# SCH_myMCP23017_2023-06-13.net
KiCad netlist of a schematic drawn in EasyEDA
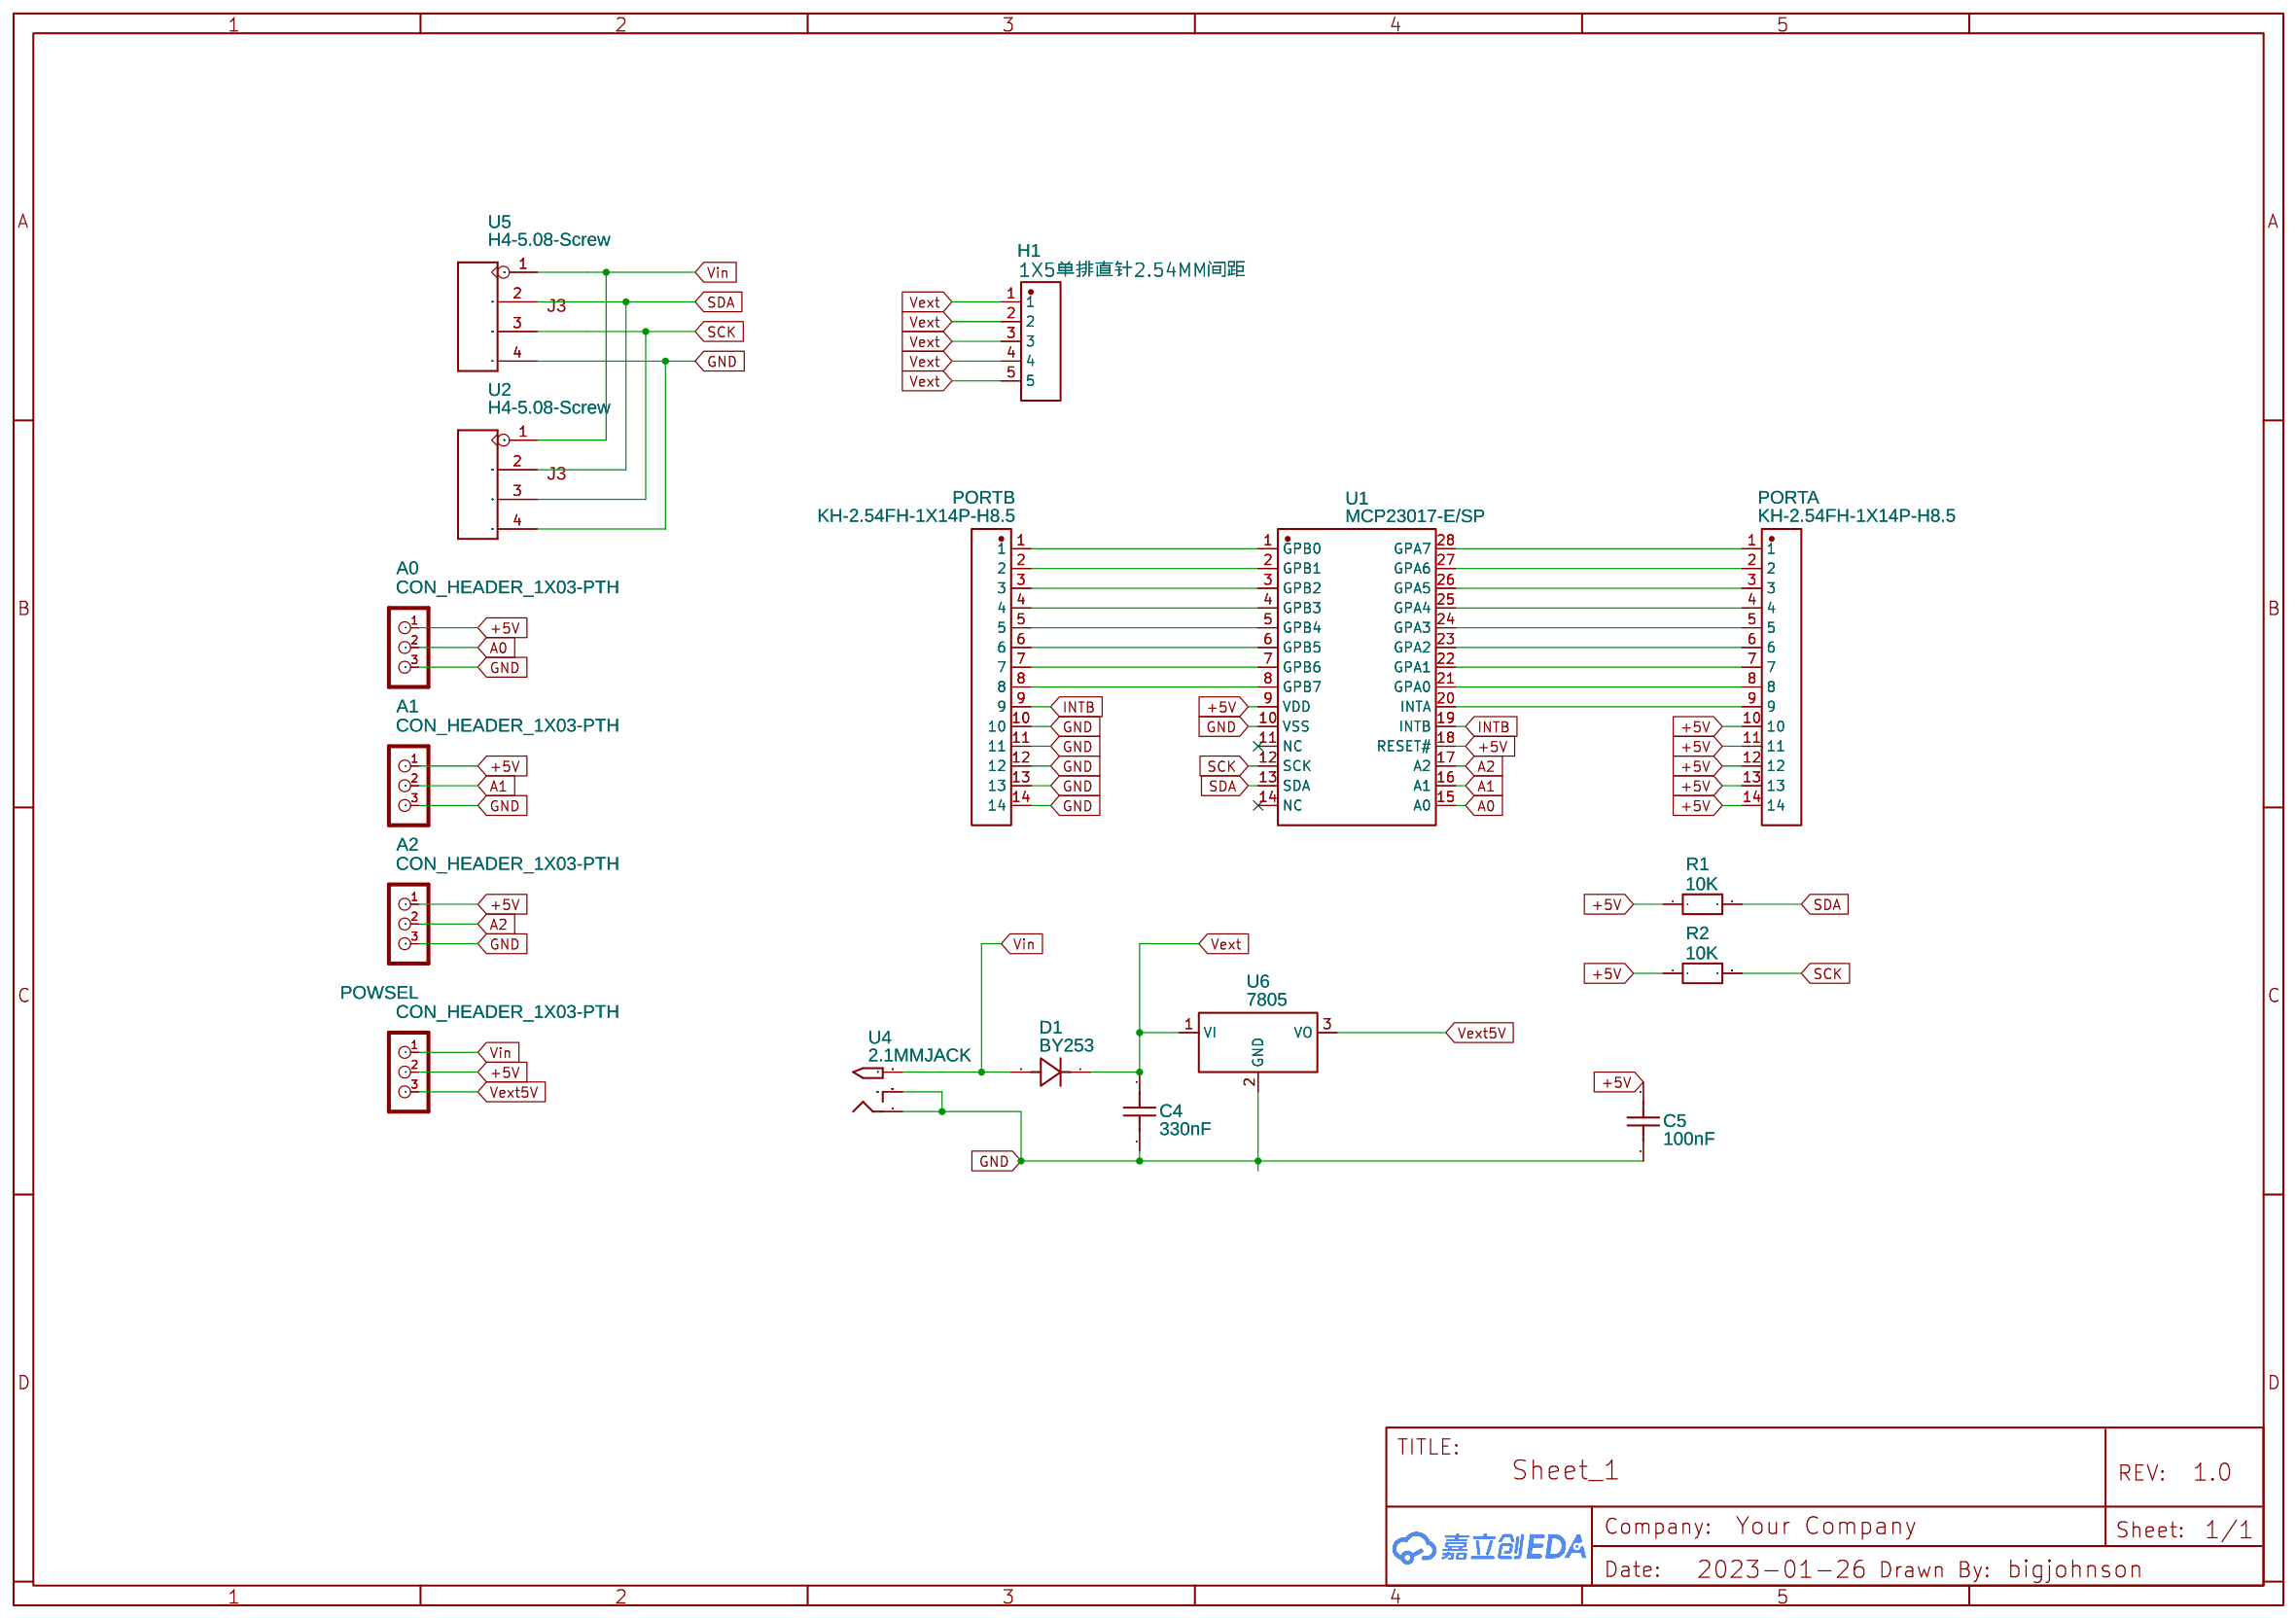
[diagram p0: schematic sheet]

(export (version "E")
  (design (tool "Eeschema 10.0.6"))
  (components
    (comp (ref "A0") (value "CON_HEADER_1X03-PTH") (libsource (lib "") (part "CON_HEADER_1X03-PTH")))
    (comp (ref "A1") (value "CON_HEADER_1X03-PTH") (libsource (lib "") (part "CON_HEADER_1X03-PTH")))
    (comp (ref "A2") (value "CON_HEADER_1X03-PTH") (libsource (lib "") (part "CON_HEADER_1X03-PTH")))
    (comp (ref "C4")
      (value "330nF")
      (fields
        (field (name "BOM_Manufacturer Part") "CT4-0805B103 K500")
        (field (name "BOM_Supplier Part") "C8033")
      )
      (libsource (lib "") (part "CT4-0805B103 K500"))
    )
    (comp (ref "C5")
      (value "100nF")
      (fields
        (field (name "BOM_Manufacturer Part") "CT4-0805B103 K500")
        (field (name "BOM_Supplier Part") "C8033")
      )
      (libsource (lib "") (part "CT4-0805B103 K500"))
    )
    (comp (ref "D1")
      (value "BY253")
      (fields (field (name "BOM_Manufacturer Part") "MUR460") (field (name "BOM_Supplier Part") "C2990844"))
      (libsource (lib "") (part "MUR460_C2990844"))
    )
    (comp (ref "H1")
      (value "1X5单排直针2.54MM间距")
      (fields
        (field (name "BOM_Manufacturer Part") "1x5单排直针2.54mm间距")
        (field (name "BOM_Supplier Part") "C9900017403")
      )
      (libsource (lib "") (part "1X5单排直针2.54MM间距"))
    )
    (comp (ref "PORTA")
      (value "KH-2.54FH-1X14P-H8.5")
      (fields (field (name "BOM_Supplier Part") "C2905420"))
      (libsource (lib "") (part "KH-2.54FH-1X14P-H8.5_1"))
    )
    (comp (ref "PORTB")
      (value "KH-2.54FH-1X14P-H8.5")
      (fields (field (name "BOM_Supplier Part") "C2905420"))
      (libsource (lib "") (part "KH-2.54FH-1X14P-H8.5"))
    )
    (comp (ref "POWSEL") (value "CON_HEADER_1X03-PTH") (libsource (lib "") (part "CON_HEADER_1X03-PTH_1")))
    (comp (ref "R1") (value "10K") (libsource (lib "") (part "Res_AXIAL-0.4(1/4W)_EU")))
    (comp (ref "R2") (value "10K") (libsource (lib "") (part "Res_AXIAL-0.4(1/4W)_EU")))
    (comp (ref "U1")
      (value "MCP23017-E/SP")
      (fields (field (name "BOM_Supplier Part") "C647352"))
      (libsource (lib "") (part "MCP23017-E/SP"))
    )
    (comp (ref "U2") (value "H4-5.08-Screw") (libsource (lib "") (part "H4-5.08-Screw")))
    (comp (ref "U4") (value "2.1MMJACK") (libsource (lib "") (part "2.1MMJACK")))
    (comp (ref "U5") (value "H4-5.08-Screw") (libsource (lib "") (part "H4-5.08-Screw")))
    (comp (ref "U6")
      (value "7805")
      (fields (field (name "BOM_Supplier Part") "C305416"))
      (libsource (lib "") (part "7805"))
    )
  )
  (nets
    (net (code "1") (name "+5V") (class "Default")
      (node (ref "A0") (pin "1") (pinfunction "1_1") (pintype "unspecified"))
      (node (ref "A1") (pin "1") (pinfunction "1_1") (pintype "unspecified"))
      (node (ref "A2") (pin "1") (pinfunction "1_1") (pintype "unspecified"))
      (node (ref "C5") (pin "1") (pinfunction "1_1") (pintype "unspecified"))
      (node (ref "PORTA") (pin "10") (pinfunction "10_10") (pintype "unspecified"))
      (node (ref "PORTA") (pin "11") (pinfunction "11_11") (pintype "unspecified"))
      (node (ref "PORTA") (pin "12") (pinfunction "12_12") (pintype "unspecified"))
      (node (ref "PORTA") (pin "13") (pinfunction "13_13") (pintype "unspecified"))
      (node (ref "PORTA") (pin "14") (pinfunction "14_14") (pintype "unspecified"))
      (node (ref "POWSEL") (pin "2") (pinfunction "2_2") (pintype "unspecified"))
      (node (ref "R1") (pin "1") (pinfunction "1_1") (pintype "unspecified"))
      (node (ref "R2") (pin "1") (pinfunction "1_1") (pintype "unspecified"))
      (node (ref "U1") (pin "18") (pinfunction "RESET#_18") (pintype "unspecified"))
      (node (ref "U1") (pin "9") (pinfunction "VDD_9") (pintype "unspecified"))
    )
    (net (code "2") (name "A0") (class "Default")
      (node (ref "A0") (pin "2") (pinfunction "2_2") (pintype "unspecified"))
      (node (ref "U1") (pin "15") (pinfunction "A0_15") (pintype "unspecified"))
    )
    (net (code "3") (name "A1") (class "Default")
      (node (ref "A1") (pin "2") (pinfunction "2_2") (pintype "unspecified"))
      (node (ref "U1") (pin "16") (pinfunction "A1_16") (pintype "unspecified"))
    )
    (net (code "4") (name "A2") (class "Default")
      (node (ref "A2") (pin "2") (pinfunction "2_2") (pintype "unspecified"))
      (node (ref "U1") (pin "17") (pinfunction "A2_17") (pintype "unspecified"))
    )
    (net (code "5") (name "GND") (class "Default")
      (node (ref "A0") (pin "3") (pinfunction "3_3") (pintype "unspecified"))
      (node (ref "A1") (pin "3") (pinfunction "3_3") (pintype "unspecified"))
      (node (ref "A2") (pin "3") (pinfunction "3_3") (pintype "unspecified"))
      (node (ref "C4") (pin "2") (pinfunction "2_2") (pintype "unspecified"))
      (node (ref "C5") (pin "2") (pinfunction "2_2") (pintype "unspecified"))
      (node (ref "PORTB") (pin "10") (pinfunction "10_10") (pintype "unspecified"))
      (node (ref "PORTB") (pin "11") (pinfunction "11_11") (pintype "unspecified"))
      (node (ref "PORTB") (pin "12") (pinfunction "12_12") (pintype "unspecified"))
      (node (ref "PORTB") (pin "13") (pinfunction "13_13") (pintype "unspecified"))
      (node (ref "PORTB") (pin "14") (pinfunction "14_14") (pintype "unspecified"))
      (node (ref "U1") (pin "10") (pinfunction "VSS_10") (pintype "unspecified"))
      (node (ref "U2") (pin "4") (pinfunction "P$4_4") (pintype "unspecified"))
      (node (ref "U4") (pin "RING") (pinfunction "RING_RING") (pintype "unspecified"))
      (node (ref "U4") (pin "RING_SW") (pinfunction "RING_SW_RING_SW") (pintype "unspecified"))
      (node (ref "U5") (pin "4") (pinfunction "P$4_4") (pintype "unspecified"))
      (node (ref "U6") (pin "2") (pinfunction "GND_2") (pintype "unspecified"))
    )
    (net (code "6") (name "INTB") (class "Default")
      (node (ref "PORTB") (pin "9") (pinfunction "9_9") (pintype "unspecified"))
      (node (ref "U1") (pin "19") (pinfunction "INTB_19") (pintype "unspecified"))
    )
    (net (code "7") (name "Net-(U1-GPA0)") (class "Default")
      (node (ref "PORTA") (pin "8") (pinfunction "8_8") (pintype "unspecified"))
      (node (ref "U1") (pin "21") (pinfunction "GPA0_21") (pintype "unspecified"))
    )
    (net (code "8") (name "Net-(U1-GPA1)") (class "Default")
      (node (ref "PORTA") (pin "7") (pinfunction "7_7") (pintype "unspecified"))
      (node (ref "U1") (pin "22") (pinfunction "GPA1_22") (pintype "unspecified"))
    )
    (net (code "9") (name "Net-(U1-GPA2)") (class "Default")
      (node (ref "PORTA") (pin "6") (pinfunction "6_6") (pintype "unspecified"))
      (node (ref "U1") (pin "23") (pinfunction "GPA2_23") (pintype "unspecified"))
    )
    (net (code "10") (name "Net-(U1-GPA3)") (class "Default")
      (node (ref "PORTA") (pin "5") (pinfunction "5_5") (pintype "unspecified"))
      (node (ref "U1") (pin "24") (pinfunction "GPA3_24") (pintype "unspecified"))
    )
    (net (code "11") (name "Net-(U1-GPA4)") (class "Default")
      (node (ref "PORTA") (pin "4") (pinfunction "4_4") (pintype "unspecified"))
      (node (ref "U1") (pin "25") (pinfunction "GPA4_25") (pintype "unspecified"))
    )
    (net (code "12") (name "Net-(U1-GPA5)") (class "Default")
      (node (ref "PORTA") (pin "3") (pinfunction "3_3") (pintype "unspecified"))
      (node (ref "U1") (pin "26") (pinfunction "GPA5_26") (pintype "unspecified"))
    )
    (net (code "13") (name "Net-(U1-GPA6)") (class "Default")
      (node (ref "PORTA") (pin "2") (pinfunction "2_2") (pintype "unspecified"))
      (node (ref "U1") (pin "27") (pinfunction "GPA6_27") (pintype "unspecified"))
    )
    (net (code "14") (name "Net-(U1-GPA7)") (class "Default")
      (node (ref "PORTA") (pin "1") (pinfunction "1_1") (pintype "unspecified"))
      (node (ref "U1") (pin "28") (pinfunction "GPA7_28") (pintype "unspecified"))
    )
    (net (code "15") (name "Net-(U1-GPB0)") (class "Default")
      (node (ref "PORTB") (pin "1") (pinfunction "1_1") (pintype "unspecified"))
      (node (ref "U1") (pin "1") (pinfunction "GPB0_1") (pintype "unspecified"))
    )
    (net (code "16") (name "Net-(U1-GPB1)") (class "Default")
      (node (ref "PORTB") (pin "2") (pinfunction "2_2") (pintype "unspecified"))
      (node (ref "U1") (pin "2") (pinfunction "GPB1_2") (pintype "unspecified"))
    )
    (net (code "17") (name "Net-(U1-GPB2)") (class "Default")
      (node (ref "PORTB") (pin "3") (pinfunction "3_3") (pintype "unspecified"))
      (node (ref "U1") (pin "3") (pinfunction "GPB2_3") (pintype "unspecified"))
    )
    (net (code "18") (name "Net-(U1-GPB3)") (class "Default")
      (node (ref "PORTB") (pin "4") (pinfunction "4_4") (pintype "unspecified"))
      (node (ref "U1") (pin "4") (pinfunction "GPB3_4") (pintype "unspecified"))
    )
    (net (code "19") (name "Net-(U1-GPB4)") (class "Default")
      (node (ref "PORTB") (pin "5") (pinfunction "5_5") (pintype "unspecified"))
      (node (ref "U1") (pin "5") (pinfunction "GPB4_5") (pintype "unspecified"))
    )
    (net (code "20") (name "Net-(U1-GPB5)") (class "Default")
      (node (ref "PORTB") (pin "6") (pinfunction "6_6") (pintype "unspecified"))
      (node (ref "U1") (pin "6") (pinfunction "GPB5_6") (pintype "unspecified"))
    )
    (net (code "21") (name "Net-(U1-GPB6)") (class "Default")
      (node (ref "PORTB") (pin "7") (pinfunction "7_7") (pintype "unspecified"))
      (node (ref "U1") (pin "7") (pinfunction "GPB6_7") (pintype "unspecified"))
    )
    (net (code "22") (name "Net-(U1-GPB7)") (class "Default")
      (node (ref "PORTB") (pin "8") (pinfunction "8_8") (pintype "unspecified"))
      (node (ref "U1") (pin "8") (pinfunction "GPB7_8") (pintype "unspecified"))
    )
    (net (code "23") (name "Net-(U1-INTA)") (class "Default")
      (node (ref "PORTA") (pin "9") (pinfunction "9_9") (pintype "unspecified"))
      (node (ref "U1") (pin "20") (pinfunction "INTA_20") (pintype "unspecified"))
    )
    (net (code "24") (name "SCK") (class "Default")
      (node (ref "R2") (pin "2") (pinfunction "2_2") (pintype "unspecified"))
      (node (ref "U1") (pin "12") (pinfunction "SCK_12") (pintype "unspecified"))
      (node (ref "U2") (pin "3") (pinfunction "P$3_3") (pintype "unspecified"))
      (node (ref "U5") (pin "3") (pinfunction "P$3_3") (pintype "unspecified"))
    )
    (net (code "25") (name "SDA") (class "Default")
      (node (ref "R1") (pin "2") (pinfunction "2_2") (pintype "unspecified"))
      (node (ref "U1") (pin "13") (pinfunction "SDA_13") (pintype "unspecified"))
      (node (ref "U2") (pin "2") (pinfunction "P$2_2") (pintype "unspecified"))
      (node (ref "U5") (pin "2") (pinfunction "P$2_2") (pintype "unspecified"))
    )
    (net (code "26") (name "Vext") (class "Default")
      (node (ref "C4") (pin "1") (pinfunction "1_1") (pintype "unspecified"))
      (node (ref "D1") (pin "1") (pinfunction "K_1") (pintype "unspecified"))
      (node (ref "H1") (pin "1") (pinfunction "1_1") (pintype "unspecified"))
      (node (ref "H1") (pin "2") (pinfunction "2_2") (pintype "unspecified"))
      (node (ref "H1") (pin "3") (pinfunction "3_3") (pintype "unspecified"))
      (node (ref "H1") (pin "4") (pinfunction "4_4") (pintype "unspecified"))
      (node (ref "H1") (pin "5") (pinfunction "5_5") (pintype "unspecified"))
      (node (ref "U6") (pin "1") (pinfunction "VI_1") (pintype "unspecified"))
    )
    (net (code "27") (name "Vext5V") (class "Default")
      (node (ref "POWSEL") (pin "3") (pinfunction "3_3") (pintype "unspecified"))
      (node (ref "U6") (pin "3") (pinfunction "VO_3") (pintype "unspecified"))
    )
    (net (code "28") (name "Vin") (class "Default")
      (node (ref "D1") (pin "2") (pinfunction "A_2") (pintype "unspecified"))
      (node (ref "POWSEL") (pin "1") (pinfunction "1_1") (pintype "unspecified"))
      (node (ref "U2") (pin "1") (pinfunction "P$1_1") (pintype "unspecified"))
      (node (ref "U4") (pin "TIP") (pinfunction "TIP_TIP") (pintype "unspecified"))
      (node (ref "U5") (pin "1") (pinfunction "P$1_1") (pintype "unspecified"))
    )
    (net (code "29") (name "unconnected-(U1-NC-Pad11)") (class "Default")
      (node (ref "U1") (pin "11") (pinfunction "NC_11") (pintype "unspecified+no_connect"))
    )
    (net (code "30") (name "unconnected-(U1-NC-Pad14)") (class "Default")
      (node (ref "U1") (pin "14") (pinfunction "NC_14") (pintype "unspecified+no_connect"))
    )
  )
)
